# ELdrv.net
KiCad netlist of a schematic drawn in EAGLE
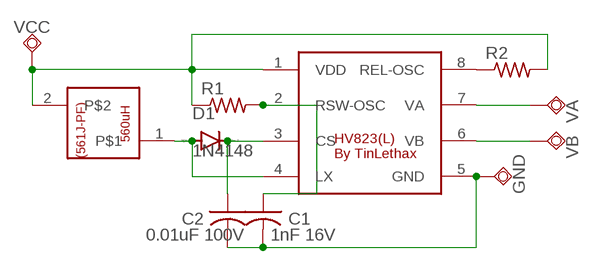
[diagram p0: schematic, sheet 1]

(export (version "E")
  (design (tool "Eeschema 10.0.6"))
  (components
    (comp (ref "C1")
      (value "1nF 16V")
      (footprint "eagle-import:C0603K")
      (libsource (lib "eagle-import") (part "C-USC0603K"))
    )
    (comp (ref "C2")
      (value "0.01uF 100V")
      (footprint "eagle-import:C025-040X050")
      (libsource (lib "eagle-import") (part "C-US025-040X050"))
    )
    (comp (ref "D1")
      (value "1N4148")
      (footprint "eagle-import:SOD-123_MINI-SMA")
      (libsource (lib "eagle-import") (part "CGRM400-G"))
    )
    (comp (ref "GND")
      (value "TPSQTP20SQ")
      (footprint "eagle-import:TP20SQ")
      (libsource (lib "eagle-import") (part "TPSQTP20SQ"))
    )
    (comp (ref "L1")
      (value "NL453232T-561J-PF")
      (footprint "eagle-import:INDC4526X50N")
      (libsource (lib "eagle-import") (part "NL453232T-561J-PF"))
    )
    (comp (ref "R1")
      (value "R-US_R0603")
      (footprint "eagle-import:R0603")
      (libsource (lib "eagle-import") (part "R-US_R0603"))
    )
    (comp (ref "R2")
      (value "R-US_R0603")
      (footprint "eagle-import:R0603")
      (libsource (lib "eagle-import") (part "R-US_R0603"))
    )
    (comp (ref "U1")
      (value "HV823")
      (footprint "eagle-import:SOIC127P600X175-9T200L")
      (libsource (lib "eagle-import") (part "HV823"))
    )
    (comp (ref "VA")
      (value "TPSQTP20SQ")
      (footprint "eagle-import:TP20SQ")
      (libsource (lib "eagle-import") (part "TPSQTP20SQ"))
    )
    (comp (ref "VB")
      (value "TPSQTP20SQ")
      (footprint "eagle-import:TP20SQ")
      (libsource (lib "eagle-import") (part "TPSQTP20SQ"))
    )
    (comp (ref "VCC")
      (value "TPSQTP20SQ")
      (footprint "eagle-import:TP20SQ")
      (libsource (lib "eagle-import") (part "TPSQTP20SQ"))
    )
  )
  (nets
    (net (code "1") (name "Net-(L1-P$1)") (class "Default")
      (node (ref "D1") (pin "A") (pinfunction "A_A") (pintype "passive"))
      (node (ref "L1") (pin "1") (pinfunction "P$1_1") (pintype "bidirectional"))
      (node (ref "U1") (pin "4") (pinfunction "LX_4") (pintype "bidirectional"))
    )
    (net (code "2") (name "Net-(L1-P$2)") (class "Default")
      (node (ref "L1") (pin "2") (pinfunction "P$2_2") (pintype "bidirectional"))
      (node (ref "R1") (pin "1") (pinfunction "1_1") (pintype "passive"))
      (node (ref "R2") (pin "2") (pinfunction "2_2") (pintype "passive"))
      (node (ref "U1") (pin "1") (pinfunction "VDD_1") (pintype "bidirectional"))
      (node (ref "VCC") (pin "TP") (pinfunction "TP_TP") (pintype "input"))
    )
    (net (code "3") (name "Net-(U1-CS)") (class "Default")
      (node (ref "C2") (pin "1") (pinfunction "1_1") (pintype "passive"))
      (node (ref "D1") (pin "C") (pinfunction "C_C") (pintype "passive"))
      (node (ref "U1") (pin "3") (pinfunction "CS_3") (pintype "bidirectional"))
    )
    (net (code "4") (name "Net-(U1-GND)") (class "Default")
      (node (ref "C1") (pin "2") (pinfunction "2_2") (pintype "passive"))
      (node (ref "C2") (pin "2") (pinfunction "2_2") (pintype "passive"))
      (node (ref "GND") (pin "TP") (pinfunction "TP_TP") (pintype "input"))
      (node (ref "U1") (pin "5") (pinfunction "GND_5") (pintype "bidirectional"))
    )
    (net (code "5") (name "Net-(U1-REL-OSC)") (class "Default")
      (node (ref "R2") (pin "1") (pinfunction "1_1") (pintype "passive"))
      (node (ref "U1") (pin "8") (pinfunction "REL-OSC_8") (pintype "bidirectional"))
    )
    (net (code "6") (name "Net-(U1-RSW-OSC)") (class "Default")
      (node (ref "C1") (pin "1") (pinfunction "1_1") (pintype "passive"))
      (node (ref "R1") (pin "2") (pinfunction "2_2") (pintype "passive"))
      (node (ref "U1") (pin "2") (pinfunction "RSW-OSC_2") (pintype "bidirectional"))
    )
    (net (code "7") (name "Net-(U1-VA)") (class "Default")
      (node (ref "U1") (pin "7") (pinfunction "VA_7") (pintype "bidirectional"))
      (node (ref "VA") (pin "TP") (pinfunction "TP_TP") (pintype "input"))
    )
    (net (code "8") (name "Net-(U1-VB)") (class "Default")
      (node (ref "U1") (pin "6") (pinfunction "VB_6") (pintype "bidirectional"))
      (node (ref "VB") (pin "TP") (pinfunction "TP_TP") (pintype "input"))
    )
  )
)
